# anookum_control.net
KiCad netlist of a schematic drawn in EAGLE
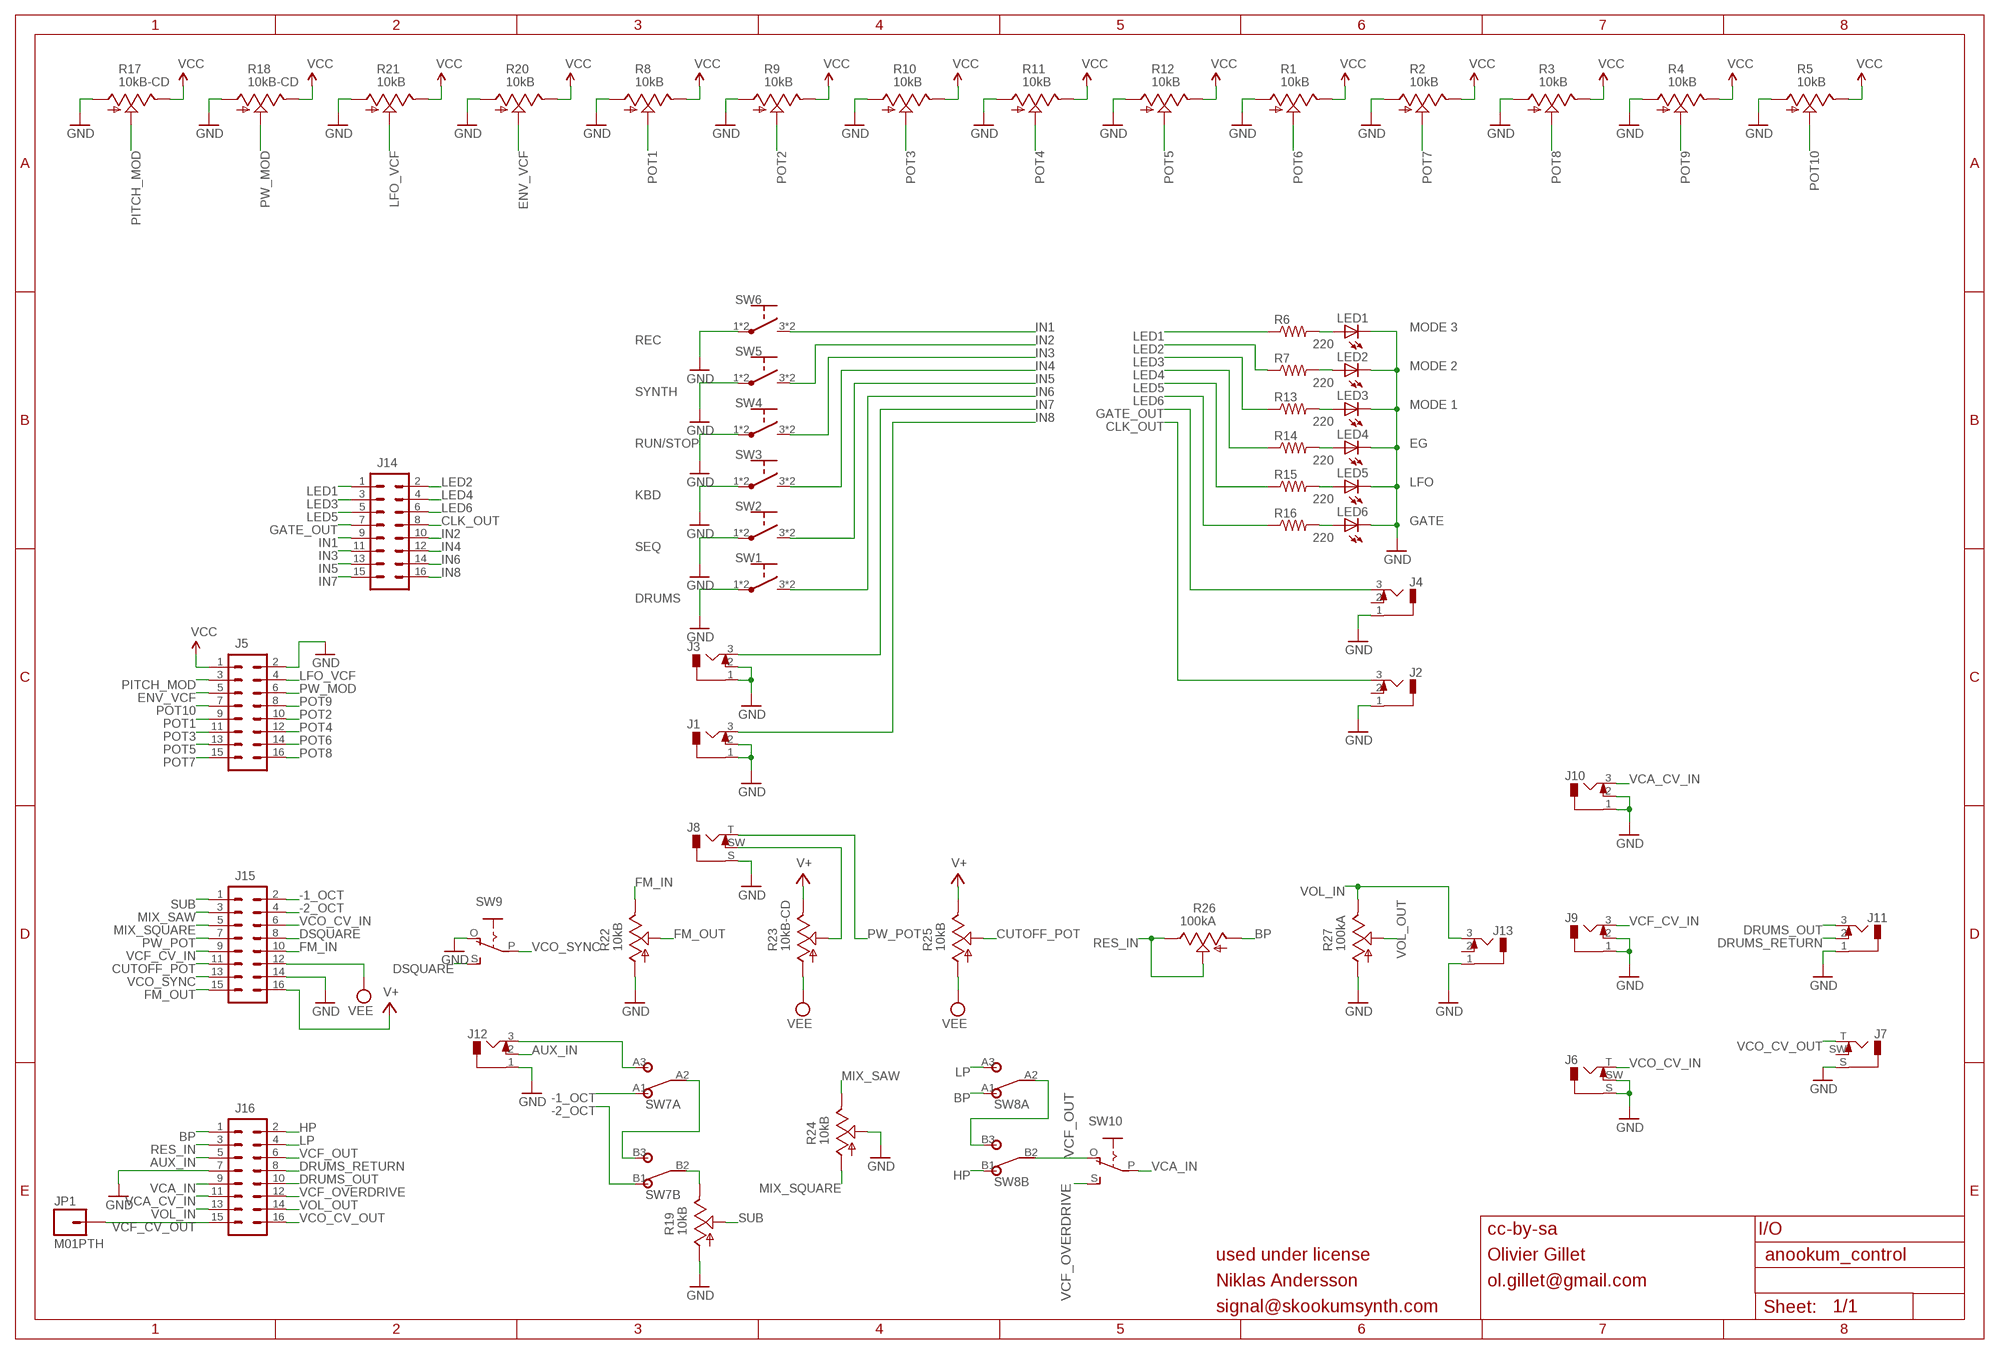
[diagram p0: schematic, sheet 1]

(export (version "E")
  (design (tool "Eeschema 10.0.6"))
  (components
    (comp (ref "J1")
      (value "JACK_MONO_SW_V")
      (footprint "eagle-import:WQP_PJ301M-12@1")
      (libsource (lib "eagle-import") (part "JACK_MONO_SW_V"))
    )
    (comp (ref "J2")
      (value "JACK_MONO_SW_V")
      (footprint "eagle-import:WQP_PJ301M-12@1")
      (libsource (lib "eagle-import") (part "JACK_MONO_SW_V"))
    )
    (comp (ref "J3")
      (value "JACK_MONO_SW_V")
      (footprint "eagle-import:WQP_PJ301M-12@1")
      (libsource (lib "eagle-import") (part "JACK_MONO_SW_V"))
    )
    (comp (ref "J4")
      (value "JACK_MONO_SW_V")
      (footprint "eagle-import:WQP_PJ301M-12@1")
      (libsource (lib "eagle-import") (part "JACK_MONO_SW_V"))
    )
    (comp (ref "J5")
      (value "M08X2")
      (footprint "eagle-import:2X8")
      (libsource (lib "eagle-import") (part "M08X2"))
    )
    (comp (ref "J6")
      (value "CONN_MONO_SW_F_V")
      (footprint "eagle-import:WQP_PJ301M-12")
      (libsource (lib "eagle-import") (part "CONN_MONO_SW_F_V"))
    )
    (comp (ref "J7")
      (value "CONN_MONO_SW_F_V")
      (footprint "eagle-import:WQP_PJ301M-12")
      (libsource (lib "eagle-import") (part "CONN_MONO_SW_F_V"))
    )
    (comp (ref "J8")
      (value "CONN_MONO_SW_F_V")
      (footprint "eagle-import:WQP_PJ301M-12")
      (libsource (lib "eagle-import") (part "CONN_MONO_SW_F_V"))
    )
    (comp (ref "J9")
      (value "JACK_MONO_SW_V")
      (footprint "eagle-import:WQP_PJ301M-12@1")
      (libsource (lib "eagle-import") (part "JACK_MONO_SW_V"))
    )
    (comp (ref "J10")
      (value "JACK_MONO_SW_V")
      (footprint "eagle-import:WQP_PJ301M-12@1")
      (libsource (lib "eagle-import") (part "JACK_MONO_SW_V"))
    )
    (comp (ref "J11")
      (value "JACK_MONO_SW_V")
      (footprint "eagle-import:WQP_PJ301M-12@1")
      (libsource (lib "eagle-import") (part "JACK_MONO_SW_V"))
    )
    (comp (ref "J12")
      (value "JACK_MONO_SW_V")
      (footprint "eagle-import:WQP_PJ301M-12@1")
      (libsource (lib "eagle-import") (part "JACK_MONO_SW_V"))
    )
    (comp (ref "J13")
      (value "JACK_MONO_SW_V")
      (footprint "eagle-import:WQP_PJ301M-12@1")
      (libsource (lib "eagle-import") (part "JACK_MONO_SW_V"))
    )
    (comp (ref "J14")
      (value "M08X2")
      (footprint "eagle-import:2X8")
      (libsource (lib "eagle-import") (part "M08X2"))
    )
    (comp (ref "J15")
      (value "M08X2")
      (footprint "eagle-import:2X8")
      (libsource (lib "eagle-import") (part "M08X2"))
    )
    (comp (ref "J16")
      (value "M08X2")
      (footprint "eagle-import:2X8")
      (libsource (lib "eagle-import") (part "M08X2"))
    )
    (comp (ref "JP1")
      (value "M01PTH")
      (footprint "eagle-import:1X01")
      (libsource (lib "eagle-import") (part "M01PTH"))
    )
    (comp (ref "LED1")
      (value "LED3MM")
      (footprint "eagle-import:LED3MM")
      (libsource (lib "eagle-import") (part "LED3MM"))
    )
    (comp (ref "LED2")
      (value "LED3MM")
      (footprint "eagle-import:LED3MM")
      (libsource (lib "eagle-import") (part "LED3MM"))
    )
    (comp (ref "LED3")
      (value "LED3MM")
      (footprint "eagle-import:LED3MM")
      (libsource (lib "eagle-import") (part "LED3MM"))
    )
    (comp (ref "LED4")
      (value "LED3MM")
      (footprint "eagle-import:LED3MM")
      (libsource (lib "eagle-import") (part "LED3MM"))
    )
    (comp (ref "LED5")
      (value "LED3MM")
      (footprint "eagle-import:LED3MM")
      (libsource (lib "eagle-import") (part "LED3MM"))
    )
    (comp (ref "LED6")
      (value "LED3MM")
      (footprint "eagle-import:LED3MM")
      (libsource (lib "eagle-import") (part "LED3MM"))
    )
    (comp (ref "R1")
      (value "10kB")
      (footprint "eagle-import:ALPS_POT_VERTICAL")
      (libsource (lib "eagle-import") (part "POT_USVERTICAL"))
    )
    (comp (ref "R2")
      (value "10kB")
      (footprint "eagle-import:ALPS_POT_VERTICAL")
      (libsource (lib "eagle-import") (part "POT_USVERTICAL"))
    )
    (comp (ref "R3")
      (value "10kB")
      (footprint "eagle-import:ALPS_POT_VERTICAL")
      (libsource (lib "eagle-import") (part "POT_USVERTICAL"))
    )
    (comp (ref "R4")
      (value "10kB")
      (footprint "eagle-import:ALPS_POT_VERTICAL")
      (libsource (lib "eagle-import") (part "POT_USVERTICAL"))
    )
    (comp (ref "R5")
      (value "10kB")
      (footprint "eagle-import:ALPS_POT_VERTICAL")
      (libsource (lib "eagle-import") (part "POT_USVERTICAL"))
    )
    (comp (ref "R6")
      (value "220")
      (footprint "eagle-import:0204_7")
      (libsource (lib "eagle-import") (part "R-US_0204/7"))
    )
    (comp (ref "R7")
      (value "220")
      (footprint "eagle-import:0204_7")
      (libsource (lib "eagle-import") (part "R-US_0204/7"))
    )
    (comp (ref "R8")
      (value "10kB")
      (footprint "eagle-import:ALPS_POT_VERTICAL")
      (libsource (lib "eagle-import") (part "POT_USVERTICAL"))
    )
    (comp (ref "R9")
      (value "10kB")
      (footprint "eagle-import:ALPS_POT_VERTICAL")
      (libsource (lib "eagle-import") (part "POT_USVERTICAL"))
    )
    (comp (ref "R10")
      (value "10kB")
      (footprint "eagle-import:ALPS_POT_VERTICAL")
      (libsource (lib "eagle-import") (part "POT_USVERTICAL"))
    )
    (comp (ref "R11")
      (value "10kB")
      (footprint "eagle-import:ALPS_POT_VERTICAL")
      (libsource (lib "eagle-import") (part "POT_USVERTICAL"))
    )
    (comp (ref "R12")
      (value "10kB")
      (footprint "eagle-import:ALPS_POT_VERTICAL")
      (libsource (lib "eagle-import") (part "POT_USVERTICAL"))
    )
    (comp (ref "R13")
      (value "220")
      (footprint "eagle-import:0204_7")
      (libsource (lib "eagle-import") (part "R-US_0204/7"))
    )
    (comp (ref "R14")
      (value "220")
      (footprint "eagle-import:0204_7")
      (libsource (lib "eagle-import") (part "R-US_0204/7"))
    )
    (comp (ref "R15")
      (value "220")
      (footprint "eagle-import:0204_7")
      (libsource (lib "eagle-import") (part "R-US_0204/7"))
    )
    (comp (ref "R16")
      (value "220")
      (footprint "eagle-import:0204_7")
      (libsource (lib "eagle-import") (part "R-US_0204/7"))
    )
    (comp (ref "R17")
      (value "10kB-CD")
      (footprint "eagle-import:ALPS_POT_VERTICAL")
      (libsource (lib "eagle-import") (part "POT_USVERTICAL"))
    )
    (comp (ref "R18")
      (value "10kB-CD")
      (footprint "eagle-import:ALPS_POT_VERTICAL")
      (libsource (lib "eagle-import") (part "POT_USVERTICAL"))
    )
    (comp (ref "R19")
      (value "10kB")
      (footprint "eagle-import:ALPS_POT_VERTICAL")
      (libsource (lib "eagle-import") (part "POT_USVERTICAL"))
    )
    (comp (ref "R20")
      (value "10kB")
      (footprint "eagle-import:ALPS_POT_VERTICAL")
      (libsource (lib "eagle-import") (part "POT_USVERTICAL"))
    )
    (comp (ref "R21")
      (value "10kB")
      (footprint "eagle-import:ALPS_POT_VERTICAL")
      (libsource (lib "eagle-import") (part "POT_USVERTICAL"))
    )
    (comp (ref "R22")
      (value "10kB")
      (footprint "eagle-import:ALPS_POT_VERTICAL")
      (libsource (lib "eagle-import") (part "POT_USVERTICAL"))
    )
    (comp (ref "R23")
      (value "10kB-CD")
      (footprint "eagle-import:ALPS_POT_VERTICAL")
      (libsource (lib "eagle-import") (part "POT_USVERTICAL"))
    )
    (comp (ref "R24")
      (value "10kB")
      (footprint "eagle-import:ALPS_POT_VERTICAL")
      (libsource (lib "eagle-import") (part "POT_USVERTICAL"))
    )
    (comp (ref "R25")
      (value "10kB")
      (footprint "eagle-import:ALPS_POT_VERTICAL")
      (libsource (lib "eagle-import") (part "POT_USVERTICAL"))
    )
    (comp (ref "R26")
      (value "100kA")
      (footprint "eagle-import:ALPS_POT_VERTICAL")
      (libsource (lib "eagle-import") (part "POT_USVERTICAL"))
    )
    (comp (ref "R27")
      (value "100kA")
      (footprint "eagle-import:ALPS_POT_VERTICAL")
      (libsource (lib "eagle-import") (part "POT_USVERTICAL"))
    )
    (comp (ref "SW1")
      (value "SW_TACTD6")
      (footprint "eagle-import:D6")
      (libsource (lib "eagle-import") (part "SW_TACTD6"))
    )
    (comp (ref "SW2")
      (value "SW_TACTD6")
      (footprint "eagle-import:D6")
      (libsource (lib "eagle-import") (part "SW_TACTD6"))
    )
    (comp (ref "SW3")
      (value "SW_TACTD6")
      (footprint "eagle-import:D6")
      (libsource (lib "eagle-import") (part "SW_TACTD6"))
    )
    (comp (ref "SW4")
      (value "SW_TACTD6")
      (footprint "eagle-import:D6")
      (libsource (lib "eagle-import") (part "SW_TACTD6"))
    )
    (comp (ref "SW5")
      (value "SW_TACTD6")
      (footprint "eagle-import:D6")
      (libsource (lib "eagle-import") (part "SW_TACTD6"))
    )
    (comp (ref "SW6")
      (value "SW_TACTD6")
      (footprint "eagle-import:D6")
      (libsource (lib "eagle-import") (part "SW_TACTD6"))
    )
    (comp (ref "SW7")
      (value "DPDT1AD6T2B4M2RE")
      (footprint "eagle-import:DPDT")
      (libsource (lib "eagle-import") (part "DPDT1AD6T2B4M2RE"))
    )
    (comp (ref "SW8")
      (value "DPDT1AD6T2B4M2RE")
      (footprint "eagle-import:DPDT")
      (libsource (lib "eagle-import") (part "DPDT1AD6T2B4M2RE"))
    )
    (comp (ref "SW9")
      (value "EG1218S")
      (footprint "eagle-import:EG1218")
      (libsource (lib "eagle-import") (part "EG1218S"))
    )
    (comp (ref "SW10")
      (value "EG1218S")
      (footprint "eagle-import:EG1218")
      (libsource (lib "eagle-import") (part "EG1218S"))
    )
  )
  (nets
    (net (code "1") (name "/-1_OCT") (class "Default")
      (node (ref "J15") (pin "2") (pinfunction "2_2") (pintype "passive"))
      (node (ref "SW7") (pin "A1") (pinfunction "1_A1") (pintype "passive"))
    )
    (net (code "2") (name "/-2_OCT") (class "Default")
      (node (ref "J15") (pin "4") (pinfunction "4_4") (pintype "passive"))
      (node (ref "SW7") (pin "B1") (pinfunction "1_B1") (pintype "passive"))
    )
    (net (code "3") (name "/AUX_IN") (class "Default")
      (node (ref "J12") (pin "2") (pinfunction "SW_2") (pintype "bidirectional"))
      (node (ref "J16") (pin "5") (pinfunction "5_5") (pintype "passive"))
    )
    (net (code "4") (name "/BP") (class "Default")
      (node (ref "J16") (pin "1") (pinfunction "1_1") (pintype "passive"))
      (node (ref "R26") (pin "P$3") (pinfunction "A_P$3") (pintype "passive"))
      (node (ref "SW8") (pin "A1") (pinfunction "1_A1") (pintype "passive"))
    )
    (net (code "5") (name "/CLK_OUT") (class "Default")
      (node (ref "J14") (pin "8") (pinfunction "8_8") (pintype "passive"))
      (node (ref "J2") (pin "3") (pinfunction "T_3") (pintype "bidirectional"))
    )
    (net (code "6") (name "/CUTOFF_POT") (class "Default")
      (node (ref "J15") (pin "11") (pinfunction "11_11") (pintype "passive"))
      (node (ref "R25") (pin "P$2") (pinfunction "S_P$2") (pintype "passive"))
    )
    (net (code "7") (name "/DRUMS_OUT") (class "Default")
      (node (ref "J11") (pin "3") (pinfunction "T_3") (pintype "bidirectional"))
      (node (ref "J16") (pin "10") (pinfunction "10_10") (pintype "passive"))
    )
    (net (code "8") (name "/DRUMS_RETURN") (class "Default")
      (node (ref "J11") (pin "2") (pinfunction "SW_2") (pintype "bidirectional"))
      (node (ref "J16") (pin "8") (pinfunction "8_8") (pintype "passive"))
    )
    (net (code "9") (name "/DSQUARE") (class "Default")
      (node (ref "J15") (pin "8") (pinfunction "8_8") (pintype "passive"))
      (node (ref "SW9") (pin "S") (pinfunction "S_S") (pintype "passive"))
    )
    (net (code "10") (name "/ENV_VCF") (class "Default")
      (node (ref "J5") (pin "5") (pinfunction "5_5") (pintype "passive"))
      (node (ref "R20") (pin "P$2") (pinfunction "S_P$2") (pintype "passive"))
    )
    (net (code "11") (name "/FM_IN") (class "Default")
      (node (ref "J15") (pin "10") (pinfunction "10_10") (pintype "passive"))
      (node (ref "R22") (pin "P$1") (pinfunction "E_P$1") (pintype "passive"))
    )
    (net (code "12") (name "/FM_OUT") (class "Default")
      (node (ref "J15") (pin "15") (pinfunction "15_15") (pintype "passive"))
      (node (ref "R22") (pin "P$2") (pinfunction "S_P$2") (pintype "passive"))
    )
    (net (code "13") (name "/GATE_OUT") (class "Default")
      (node (ref "J14") (pin "7") (pinfunction "7_7") (pintype "passive"))
      (node (ref "J4") (pin "3") (pinfunction "T_3") (pintype "bidirectional"))
    )
    (net (code "14") (name "/HP") (class "Default")
      (node (ref "J16") (pin "2") (pinfunction "2_2") (pintype "passive"))
      (node (ref "SW8") (pin "B1") (pinfunction "1_B1") (pintype "passive"))
    )
    (net (code "15") (name "/IN1") (class "Default")
      (node (ref "J14") (pin "9") (pinfunction "9_9") (pintype "passive"))
      (node (ref "SW6") (pin "3") (pinfunction "2_3") (pintype "passive"))
      (node (ref "SW6") (pin "4") (pinfunction "2_4") (pintype "passive"))
    )
    (net (code "16") (name "/IN2") (class "Default")
      (node (ref "J14") (pin "10") (pinfunction "10_10") (pintype "passive"))
      (node (ref "SW5") (pin "3") (pinfunction "2_3") (pintype "passive"))
      (node (ref "SW5") (pin "4") (pinfunction "2_4") (pintype "passive"))
    )
    (net (code "17") (name "/IN3") (class "Default")
      (node (ref "J14") (pin "11") (pinfunction "11_11") (pintype "passive"))
      (node (ref "SW4") (pin "3") (pinfunction "2_3") (pintype "passive"))
      (node (ref "SW4") (pin "4") (pinfunction "2_4") (pintype "passive"))
    )
    (net (code "18") (name "/IN4") (class "Default")
      (node (ref "J14") (pin "12") (pinfunction "12_12") (pintype "passive"))
      (node (ref "SW3") (pin "3") (pinfunction "2_3") (pintype "passive"))
      (node (ref "SW3") (pin "4") (pinfunction "2_4") (pintype "passive"))
    )
    (net (code "19") (name "/IN5") (class "Default")
      (node (ref "J14") (pin "13") (pinfunction "13_13") (pintype "passive"))
      (node (ref "SW2") (pin "3") (pinfunction "2_3") (pintype "passive"))
      (node (ref "SW2") (pin "4") (pinfunction "2_4") (pintype "passive"))
    )
    (net (code "20") (name "/IN6") (class "Default")
      (node (ref "J14") (pin "14") (pinfunction "14_14") (pintype "passive"))
      (node (ref "SW1") (pin "3") (pinfunction "2_3") (pintype "passive"))
      (node (ref "SW1") (pin "4") (pinfunction "2_4") (pintype "passive"))
    )
    (net (code "21") (name "/IN7") (class "Default")
      (node (ref "J14") (pin "15") (pinfunction "15_15") (pintype "passive"))
      (node (ref "J3") (pin "3") (pinfunction "T_3") (pintype "bidirectional"))
    )
    (net (code "22") (name "/IN8") (class "Default")
      (node (ref "J1") (pin "3") (pinfunction "T_3") (pintype "bidirectional"))
      (node (ref "J14") (pin "16") (pinfunction "16_16") (pintype "passive"))
    )
    (net (code "23") (name "/LED1") (class "Default")
      (node (ref "J14") (pin "1") (pinfunction "1_1") (pintype "passive"))
      (node (ref "R6") (pin "1") (pinfunction "1_1") (pintype "passive"))
    )
    (net (code "24") (name "/LED2") (class "Default")
      (node (ref "J14") (pin "2") (pinfunction "2_2") (pintype "passive"))
      (node (ref "R7") (pin "1") (pinfunction "1_1") (pintype "passive"))
    )
    (net (code "25") (name "/LED3") (class "Default")
      (node (ref "J14") (pin "3") (pinfunction "3_3") (pintype "passive"))
      (node (ref "R13") (pin "1") (pinfunction "1_1") (pintype "passive"))
    )
    (net (code "26") (name "/LED4") (class "Default")
      (node (ref "J14") (pin "4") (pinfunction "4_4") (pintype "passive"))
      (node (ref "R14") (pin "1") (pinfunction "1_1") (pintype "passive"))
    )
    (net (code "27") (name "/LED5") (class "Default")
      (node (ref "J14") (pin "5") (pinfunction "5_5") (pintype "passive"))
      (node (ref "R15") (pin "1") (pinfunction "1_1") (pintype "passive"))
    )
    (net (code "28") (name "/LED6") (class "Default")
      (node (ref "J14") (pin "6") (pinfunction "6_6") (pintype "passive"))
      (node (ref "R16") (pin "1") (pinfunction "1_1") (pintype "passive"))
    )
    (net (code "29") (name "/LFO_VCF") (class "Default")
      (node (ref "J5") (pin "4") (pinfunction "4_4") (pintype "passive"))
      (node (ref "R21") (pin "P$2") (pinfunction "S_P$2") (pintype "passive"))
    )
    (net (code "30") (name "/LP") (class "Default")
      (node (ref "J16") (pin "4") (pinfunction "4_4") (pintype "passive"))
      (node (ref "SW8") (pin "A3") (pinfunction "3_A3") (pintype "passive"))
    )
    (net (code "31") (name "/MIX_SAW") (class "Default")
      (node (ref "J15") (pin "3") (pinfunction "3_3") (pintype "passive"))
      (node (ref "R24") (pin "P$1") (pinfunction "E_P$1") (pintype "passive"))
    )
    (net (code "32") (name "/MIX_SQUARE") (class "Default")
      (node (ref "J15") (pin "5") (pinfunction "5_5") (pintype "passive"))
      (node (ref "R24") (pin "P$3") (pinfunction "A_P$3") (pintype "passive"))
    )
    (net (code "33") (name "/PITCH_MOD") (class "Default")
      (node (ref "J5") (pin "3") (pinfunction "3_3") (pintype "passive"))
      (node (ref "R17") (pin "P$2") (pinfunction "S_P$2") (pintype "passive"))
    )
    (net (code "34") (name "/POT1") (class "Default")
      (node (ref "J5") (pin "9") (pinfunction "9_9") (pintype "passive"))
      (node (ref "R8") (pin "P$2") (pinfunction "S_P$2") (pintype "passive"))
    )
    (net (code "35") (name "/POT2") (class "Default")
      (node (ref "J5") (pin "10") (pinfunction "10_10") (pintype "passive"))
      (node (ref "R9") (pin "P$2") (pinfunction "S_P$2") (pintype "passive"))
    )
    (net (code "36") (name "/POT3") (class "Default")
      (node (ref "J5") (pin "11") (pinfunction "11_11") (pintype "passive"))
      (node (ref "R10") (pin "P$2") (pinfunction "S_P$2") (pintype "passive"))
    )
    (net (code "37") (name "/POT4") (class "Default")
      (node (ref "J5") (pin "12") (pinfunction "12_12") (pintype "passive"))
      (node (ref "R11") (pin "P$2") (pinfunction "S_P$2") (pintype "passive"))
    )
    (net (code "38") (name "/POT5") (class "Default")
      (node (ref "J5") (pin "13") (pinfunction "13_13") (pintype "passive"))
      (node (ref "R12") (pin "P$2") (pinfunction "S_P$2") (pintype "passive"))
    )
    (net (code "39") (name "/POT6") (class "Default")
      (node (ref "J5") (pin "14") (pinfunction "14_14") (pintype "passive"))
      (node (ref "R1") (pin "P$2") (pinfunction "S_P$2") (pintype "passive"))
    )
    (net (code "40") (name "/POT7") (class "Default")
      (node (ref "J5") (pin "15") (pinfunction "15_15") (pintype "passive"))
      (node (ref "R2") (pin "P$2") (pinfunction "S_P$2") (pintype "passive"))
    )
    (net (code "41") (name "/POT8") (class "Default")
      (node (ref "J5") (pin "16") (pinfunction "16_16") (pintype "passive"))
      (node (ref "R3") (pin "P$2") (pinfunction "S_P$2") (pintype "passive"))
    )
    (net (code "42") (name "/POT9") (class "Default")
      (node (ref "J5") (pin "8") (pinfunction "8_8") (pintype "passive"))
      (node (ref "R4") (pin "P$2") (pinfunction "S_P$2") (pintype "passive"))
    )
    (net (code "43") (name "/POT10") (class "Default")
      (node (ref "J5") (pin "7") (pinfunction "7_7") (pintype "passive"))
      (node (ref "R5") (pin "P$2") (pinfunction "S_P$2") (pintype "passive"))
    )
    (net (code "44") (name "/PW_MOD") (class "Default")
      (node (ref "J5") (pin "6") (pinfunction "6_6") (pintype "passive"))
      (node (ref "R18") (pin "P$2") (pinfunction "S_P$2") (pintype "passive"))
    )
    (net (code "45") (name "/PW_POT") (class "Default")
      (node (ref "J15") (pin "7") (pinfunction "7_7") (pintype "passive"))
      (node (ref "J8") (pin "T") (pinfunction "T_T") (pintype "bidirectional"))
    )
    (net (code "46") (name "/RES_IN") (class "Default")
      (node (ref "J16") (pin "3") (pinfunction "3_3") (pintype "passive"))
      (node (ref "R26") (pin "P$1") (pinfunction "E_P$1") (pintype "passive"))
      (node (ref "R26") (pin "P$2") (pinfunction "S_P$2") (pintype "passive"))
    )
    (net (code "47") (name "/SUB") (class "Default")
      (node (ref "J15") (pin "1") (pinfunction "1_1") (pintype "passive"))
      (node (ref "R19") (pin "P$2") (pinfunction "S_P$2") (pintype "passive"))
    )
    (net (code "48") (name "/VCA_CV_IN") (class "Default")
      (node (ref "J10") (pin "3") (pinfunction "T_3") (pintype "bidirectional"))
      (node (ref "J16") (pin "11") (pinfunction "11_11") (pintype "passive"))
    )
    (net (code "49") (name "/VCA_IN") (class "Default")
      (node (ref "J16") (pin "9") (pinfunction "9_9") (pintype "passive"))
      (node (ref "SW10") (pin "P") (pinfunction "P_P") (pintype "passive"))
    )
    (net (code "50") (name "/VCF_CV_IN") (class "Default")
      (node (ref "J15") (pin "9") (pinfunction "9_9") (pintype "passive"))
      (node (ref "J9") (pin "3") (pinfunction "T_3") (pintype "bidirectional"))
    )
    (net (code "51") (name "/VCF_CV_OUT") (class "Default")
      (node (ref "J16") (pin "15") (pinfunction "15_15") (pintype "passive"))
      (node (ref "JP1") (pin "1") (pinfunction "1_1") (pintype "passive"))
    )
    (net (code "52") (name "/VCF_OUT") (class "Default")
      (node (ref "J16") (pin "6") (pinfunction "6_6") (pintype "passive"))
      (node (ref "SW10") (pin "O") (pinfunction "O_O") (pintype "passive"))
      (node (ref "SW8") (pin "B2") (pinfunction "2_B2") (pintype "passive"))
    )
    (net (code "53") (name "/VCF_OVERDRIVE") (class "Default")
      (node (ref "J16") (pin "12") (pinfunction "12_12") (pintype "passive"))
      (node (ref "SW10") (pin "S") (pinfunction "S_S") (pintype "passive"))
    )
    (net (code "54") (name "/VCO_CV_IN") (class "Default")
      (node (ref "J15") (pin "6") (pinfunction "6_6") (pintype "passive"))
      (node (ref "J6") (pin "T") (pinfunction "T_T") (pintype "bidirectional"))
    )
    (net (code "55") (name "/VCO_CV_OUT") (class "Default")
      (node (ref "J16") (pin "16") (pinfunction "16_16") (pintype "passive"))
      (node (ref "J7") (pin "T") (pinfunction "T_T") (pintype "bidirectional"))
    )
    (net (code "56") (name "/VCO_SYNC") (class "Default")
      (node (ref "J15") (pin "13") (pinfunction "13_13") (pintype "passive"))
      (node (ref "SW9") (pin "P") (pinfunction "P_P") (pintype "passive"))
    )
    (net (code "57") (name "/VOL_IN") (class "Default")
      (node (ref "J13") (pin "3") (pinfunction "T_3") (pintype "bidirectional"))
      (node (ref "J16") (pin "13") (pinfunction "13_13") (pintype "passive"))
      (node (ref "R27") (pin "P$1") (pinfunction "E_P$1") (pintype "passive"))
    )
    (net (code "58") (name "/VOL_OUT") (class "Default")
      (node (ref "J16") (pin "14") (pinfunction "14_14") (pintype "passive"))
      (node (ref "R27") (pin "P$2") (pinfunction "S_P$2") (pintype "passive"))
    )
    (net (code "59") (name "GND") (class "Default")
      (node (ref "J1") (pin "1") (pinfunction "S_1") (pintype "bidirectional"))
      (node (ref "J1") (pin "2") (pinfunction "SW_2") (pintype "bidirectional"))
      (node (ref "J10") (pin "1") (pinfunction "S_1") (pintype "bidirectional"))
      (node (ref "J10") (pin "2") (pinfunction "SW_2") (pintype "bidirectional"))
      (node (ref "J11") (pin "1") (pinfunction "S_1") (pintype "bidirectional"))
      (node (ref "J12") (pin "1") (pinfunction "S_1") (pintype "bidirectional"))
      (node (ref "J13") (pin "1") (pinfunction "S_1") (pintype "bidirectional"))
      (node (ref "J15") (pin "14") (pinfunction "14_14") (pintype "passive"))
      (node (ref "J16") (pin "7") (pinfunction "7_7") (pintype "passive"))
      (node (ref "J2") (pin "1") (pinfunction "S_1") (pintype "bidirectional"))
      (node (ref "J3") (pin "1") (pinfunction "S_1") (pintype "bidirectional"))
      (node (ref "J3") (pin "2") (pinfunction "SW_2") (pintype "bidirectional"))
      (node (ref "J4") (pin "1") (pinfunction "S_1") (pintype "bidirectional"))
      (node (ref "J5") (pin "2") (pinfunction "2_2") (pintype "passive"))
      (node (ref "J6") (pin "S") (pinfunction "S_S") (pintype "bidirectional"))
      (node (ref "J6") (pin "SW") (pinfunction "SW_SW") (pintype "bidirectional"))
      (node (ref "J7") (pin "S") (pinfunction "S_S") (pintype "bidirectional"))
      (node (ref "J8") (pin "S") (pinfunction "S_S") (pintype "bidirectional"))
      (node (ref "J9") (pin "1") (pinfunction "S_1") (pintype "bidirectional"))
      (node (ref "J9") (pin "2") (pinfunction "SW_2") (pintype "bidirectional"))
      (node (ref "LED1") (pin "K") (pinfunction "C_K") (pintype "passive"))
      (node (ref "LED2") (pin "K") (pinfunction "C_K") (pintype "passive"))
      (node (ref "LED3") (pin "K") (pinfunction "C_K") (pintype "passive"))
      (node (ref "LED4") (pin "K") (pinfunction "C_K") (pintype "passive"))
      (node (ref "LED5") (pin "K") (pinfunction "C_K") (pintype "passive"))
      (node (ref "LED6") (pin "K") (pinfunction "C_K") (pintype "passive"))
      (node (ref "R1") (pin "P$3") (pinfunction "A_P$3") (pintype "passive"))
      (node (ref "R10") (pin "P$3") (pinfunction "A_P$3") (pintype "passive"))
      (node (ref "R11") (pin "P$3") (pinfunction "A_P$3") (pintype "passive"))
      (node (ref "R12") (pin "P$3") (pinfunction "A_P$3") (pintype "passive"))
      (node (ref "R17") (pin "P$3") (pinfunction "A_P$3") (pintype "passive"))
      (node (ref "R18") (pin "P$3") (pinfunction "A_P$3") (pintype "passive"))
      (node (ref "R19") (pin "P$3") (pinfunction "A_P$3") (pintype "passive"))
      (node (ref "R2") (pin "P$3") (pinfunction "A_P$3") (pintype "passive"))
      (node (ref "R20") (pin "P$3") (pinfunction "A_P$3") (pintype "passive"))
      (node (ref "R21") (pin "P$3") (pinfunction "A_P$3") (pintype "passive"))
      (node (ref "R22") (pin "P$3") (pinfunction "A_P$3") (pintype "passive"))
      (node (ref "R24") (pin "P$2") (pinfunction "S_P$2") (pintype "passive"))
      (node (ref "R27") (pin "P$3") (pinfunction "A_P$3") (pintype "passive"))
      (node (ref "R3") (pin "P$3") (pinfunction "A_P$3") (pintype "passive"))
      (node (ref "R4") (pin "P$3") (pinfunction "A_P$3") (pintype "passive"))
      (node (ref "R5") (pin "P$3") (pinfunction "A_P$3") (pintype "passive"))
      (node (ref "R8") (pin "P$3") (pinfunction "A_P$3") (pintype "passive"))
      (node (ref "R9") (pin "P$3") (pinfunction "A_P$3") (pintype "passive"))
      (node (ref "SW1") (pin "1") (pinfunction "1_1") (pintype "passive"))
      (node (ref "SW1") (pin "2") (pinfunction "1_2") (pintype "passive"))
      (node (ref "SW2") (pin "1") (pinfunction "1_1") (pintype "passive"))
      (node (ref "SW2") (pin "2") (pinfunction "1_2") (pintype "passive"))
      (node (ref "SW3") (pin "1") (pinfunction "1_1") (pintype "passive"))
      (node (ref "SW3") (pin "2") (pinfunction "1_2") (pintype "passive"))
      (node (ref "SW4") (pin "1") (pinfunction "1_1") (pintype "passive"))
      (node (ref "SW4") (pin "2") (pinfunction "1_2") (pintype "passive"))
      (node (ref "SW5") (pin "1") (pinfunction "1_1") (pintype "passive"))
      (node (ref "SW5") (pin "2") (pinfunction "1_2") (pintype "passive"))
      (node (ref "SW6") (pin "1") (pinfunction "1_1") (pintype "passive"))
      (node (ref "SW6") (pin "2") (pinfunction "1_2") (pintype "passive"))
      (node (ref "SW9") (pin "O") (pinfunction "O_O") (pintype "passive"))
    )
    (net (code "60") (name "Net-(J12-T)") (class "Default")
      (node (ref "J12") (pin "3") (pinfunction "T_3") (pintype "bidirectional"))
      (node (ref "SW7") (pin "A3") (pinfunction "3_A3") (pintype "passive"))
    )
    (net (code "61") (name "Net-(LED1-PadA)") (class "Default")
      (node (ref "LED1") (pin "A") (pinfunction "A_A") (pintype "passive"))
      (node (ref "R6") (pin "2") (pinfunction "2_2") (pintype "passive"))
    )
    (net (code "62") (name "Net-(LED2-PadA)") (class "Default")
      (node (ref "LED2") (pin "A") (pinfunction "A_A") (pintype "passive"))
      (node (ref "R7") (pin "2") (pinfunction "2_2") (pintype "passive"))
    )
    (net (code "63") (name "Net-(LED3-PadA)") (class "Default")
      (node (ref "LED3") (pin "A") (pinfunction "A_A") (pintype "passive"))
      (node (ref "R13") (pin "2") (pinfunction "2_2") (pintype "passive"))
    )
    (net (code "64") (name "Net-(LED4-PadA)") (class "Default")
      (node (ref "LED4") (pin "A") (pinfunction "A_A") (pintype "passive"))
      (node (ref "R14") (pin "2") (pinfunction "2_2") (pintype "passive"))
    )
    (net (code "65") (name "Net-(LED5-PadA)") (class "Default")
      (node (ref "LED5") (pin "A") (pinfunction "A_A") (pintype "passive"))
      (node (ref "R15") (pin "2") (pinfunction "2_2") (pintype "passive"))
    )
    (net (code "66") (name "Net-(LED6-PadA)") (class "Default")
      (node (ref "LED6") (pin "A") (pinfunction "A_A") (pintype "passive"))
      (node (ref "R16") (pin "2") (pinfunction "2_2") (pintype "passive"))
    )
    (net (code "67") (name "Net-(R19-E)") (class "Default")
      (node (ref "R19") (pin "P$1") (pinfunction "E_P$1") (pintype "passive"))
      (node (ref "SW7") (pin "B2") (pinfunction "2_B2") (pintype "passive"))
    )
    (net (code "68") (name "Net-(R23-S)") (class "Default")
      (node (ref "J8") (pin "SW") (pinfunction "SW_SW") (pintype "bidirectional"))
      (node (ref "R23") (pin "P$2") (pinfunction "S_P$2") (pintype "passive"))
    )
    (net (code "69") (name "Net-(SW7A-2)") (class "Default")
      (node (ref "SW7") (pin "A2") (pinfunction "2_A2") (pintype "passive"))
      (node (ref "SW7") (pin "B3") (pinfunction "3_B3") (pintype "passive"))
    )
    (net (code "70") (name "Net-(SW8A-2)") (class "Default")
      (node (ref "SW8") (pin "A2") (pinfunction "2_A2") (pintype "passive"))
      (node (ref "SW8") (pin "B3") (pinfunction "3_B3") (pintype "passive"))
    )
    (net (code "71") (name "V+") (class "Default")
      (node (ref "J15") (pin "16") (pinfunction "16_16") (pintype "passive"))
      (node (ref "R23") (pin "P$1") (pinfunction "E_P$1") (pintype "passive"))
      (node (ref "R25") (pin "P$1") (pinfunction "E_P$1") (pintype "passive"))
    )
    (net (code "72") (name "VCC") (class "Default")
      (node (ref "J5") (pin "1") (pinfunction "1_1") (pintype "passive"))
      (node (ref "R1") (pin "P$1") (pinfunction "E_P$1") (pintype "passive"))
      (node (ref "R10") (pin "P$1") (pinfunction "E_P$1") (pintype "passive"))
      (node (ref "R11") (pin "P$1") (pinfunction "E_P$1") (pintype "passive"))
      (node (ref "R12") (pin "P$1") (pinfunction "E_P$1") (pintype "passive"))
      (node (ref "R17") (pin "P$1") (pinfunction "E_P$1") (pintype "passive"))
      (node (ref "R18") (pin "P$1") (pinfunction "E_P$1") (pintype "passive"))
      (node (ref "R2") (pin "P$1") (pinfunction "E_P$1") (pintype "passive"))
      (node (ref "R20") (pin "P$1") (pinfunction "E_P$1") (pintype "passive"))
      (node (ref "R21") (pin "P$1") (pinfunction "E_P$1") (pintype "passive"))
      (node (ref "R3") (pin "P$1") (pinfunction "E_P$1") (pintype "passive"))
      (node (ref "R4") (pin "P$1") (pinfunction "E_P$1") (pintype "passive"))
      (node (ref "R5") (pin "P$1") (pinfunction "E_P$1") (pintype "passive"))
      (node (ref "R8") (pin "P$1") (pinfunction "E_P$1") (pintype "passive"))
      (node (ref "R9") (pin "P$1") (pinfunction "E_P$1") (pintype "passive"))
    )
    (net (code "73") (name "VEE") (class "Default")
      (node (ref "J15") (pin "12") (pinfunction "12_12") (pintype "passive"))
      (node (ref "R23") (pin "P$3") (pinfunction "A_P$3") (pintype "passive"))
      (node (ref "R25") (pin "P$3") (pinfunction "A_P$3") (pintype "passive"))
    )
    (net (code "74") (name "unconnected-(J2-SW-Pad2)") (class "Default")
      (node (ref "J2") (pin "2") (pinfunction "SW_2") (pintype "bidirectional"))
    )
    (net (code "75") (name "unconnected-(J4-SW-Pad2)") (class "Default")
      (node (ref "J4") (pin "2") (pinfunction "SW_2") (pintype "bidirectional"))
    )
    (net (code "76") (name "unconnected-(J7-PadSW)") (class "Default")
      (node (ref "J7") (pin "SW") (pinfunction "SW_SW") (pintype "bidirectional"))
    )
    (net (code "77") (name "unconnected-(J13-SW-Pad2)") (class "Default")
      (node (ref "J13") (pin "2") (pinfunction "SW_2") (pintype "bidirectional"))
    )
  )
)
